# LSM6DS3Board1.net
KiCad netlist of a schematic drawn in EAGLE
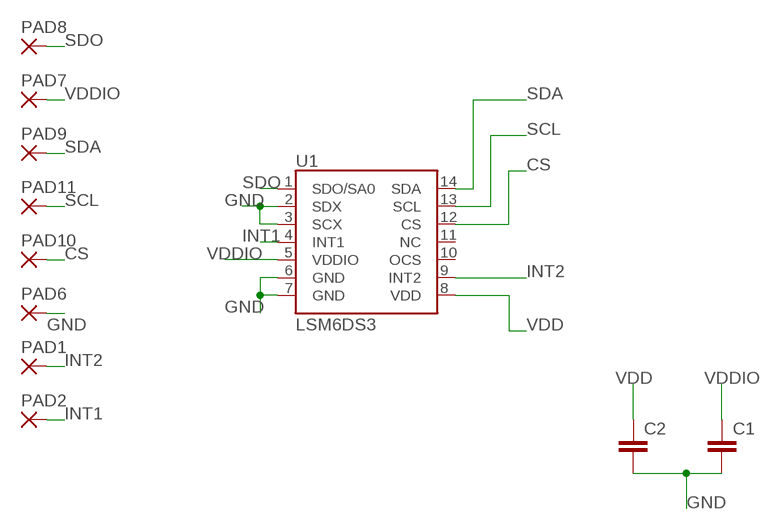
[diagram p0: schematic, sheet 1]

(export (version "E")
  (design (tool "Eeschema 10.0.6"))
  (components
    (comp (ref "C1")
      (value "C-EUC0603")
      (footprint "eagle-import:C0603")
      (libsource (lib "eagle-import") (part "C-EUC0603"))
    )
    (comp (ref "C2")
      (value "C-EUC0603")
      (footprint "eagle-import:C0603")
      (libsource (lib "eagle-import") (part "C-EUC0603"))
    )
    (comp (ref "PAD1")
      (value "1,6/0,8")
      (footprint "eagle-import:1,6_0,8")
      (libsource (lib "eagle-import") (part "1,6/0,8"))
    )
    (comp (ref "PAD2")
      (value "1,6/0,8")
      (footprint "eagle-import:1,6_0,8")
      (libsource (lib "eagle-import") (part "1,6/0,8"))
    )
    (comp (ref "PAD6")
      (value "1,6/0,8")
      (footprint "eagle-import:1,6_0,8")
      (libsource (lib "eagle-import") (part "1,6/0,8"))
    )
    (comp (ref "PAD7")
      (value "1,6/0,8")
      (footprint "eagle-import:1,6_0,8")
      (libsource (lib "eagle-import") (part "1,6/0,8"))
    )
    (comp (ref "PAD8")
      (value "1,6/0,8")
      (footprint "eagle-import:1,6_0,8")
      (libsource (lib "eagle-import") (part "1,6/0,8"))
    )
    (comp (ref "PAD9")
      (value "1,6/0,8")
      (footprint "eagle-import:1,6_0,8")
      (libsource (lib "eagle-import") (part "1,6/0,8"))
    )
    (comp (ref "PAD10")
      (value "1,6/0,8")
      (footprint "eagle-import:1,6_0,8")
      (libsource (lib "eagle-import") (part "1,6/0,8"))
    )
    (comp (ref "PAD11")
      (value "1,6/0,8")
      (footprint "eagle-import:1,6_0,8")
      (libsource (lib "eagle-import") (part "1,6/0,8"))
    )
    (comp (ref "U1")
      (value "LSM6DS3")
      (footprint "eagle-import:LGA14L")
      (libsource (lib "eagle-import") (part "LSM6DS3"))
    )
  )
  (nets
    (net (code "1") (name "/CS") (class "Default")
      (node (ref "PAD10") (pin "1") (pinfunction "P_1") (pintype "passive"))
      (node (ref "U1") (pin "12") (pinfunction "CS_12") (pintype "bidirectional"))
    )
    (net (code "2") (name "/GND") (class "Default")
      (node (ref "C1") (pin "2") (pinfunction "2_2") (pintype "passive"))
      (node (ref "C2") (pin "2") (pinfunction "2_2") (pintype "passive"))
      (node (ref "PAD6") (pin "1") (pinfunction "P_1") (pintype "passive"))
      (node (ref "U1") (pin "2") (pinfunction "SDX_2") (pintype "bidirectional"))
      (node (ref "U1") (pin "3") (pinfunction "SCX_3") (pintype "bidirectional"))
      (node (ref "U1") (pin "6") (pinfunction "GND_6") (pintype "bidirectional"))
      (node (ref "U1") (pin "7") (pinfunction "GND_7") (pintype "bidirectional"))
    )
    (net (code "3") (name "/INT1") (class "Default")
      (node (ref "PAD2") (pin "1") (pinfunction "P_1") (pintype "passive"))
      (node (ref "U1") (pin "4") (pinfunction "INT1_4") (pintype "bidirectional"))
    )
    (net (code "4") (name "/INT2") (class "Default")
      (node (ref "PAD1") (pin "1") (pinfunction "P_1") (pintype "passive"))
      (node (ref "U1") (pin "9") (pinfunction "INT2_9") (pintype "bidirectional"))
    )
    (net (code "5") (name "/SCL") (class "Default")
      (node (ref "PAD11") (pin "1") (pinfunction "P_1") (pintype "passive"))
      (node (ref "U1") (pin "13") (pinfunction "SCL_13") (pintype "bidirectional"))
    )
    (net (code "6") (name "/SDA") (class "Default")
      (node (ref "PAD9") (pin "1") (pinfunction "P_1") (pintype "passive"))
      (node (ref "U1") (pin "14") (pinfunction "SDA_14") (pintype "bidirectional"))
    )
    (net (code "7") (name "/SDO") (class "Default")
      (node (ref "PAD8") (pin "1") (pinfunction "P_1") (pintype "passive"))
      (node (ref "U1") (pin "1") (pinfunction "SDO/SA0_1") (pintype "bidirectional"))
    )
    (net (code "8") (name "/VDD") (class "Default")
      (node (ref "C2") (pin "1") (pinfunction "1_1") (pintype "passive"))
      (node (ref "U1") (pin "8") (pinfunction "VDD_8") (pintype "bidirectional"))
    )
    (net (code "9") (name "/VDDIO") (class "Default")
      (node (ref "C1") (pin "1") (pinfunction "1_1") (pintype "passive"))
      (node (ref "PAD7") (pin "1") (pinfunction "P_1") (pintype "passive"))
      (node (ref "U1") (pin "5") (pinfunction "VDDIO_5") (pintype "bidirectional"))
    )
    (net (code "10") (name "unconnected-(U1-NC-Pad11)") (class "Default")
      (node (ref "U1") (pin "11") (pinfunction "NC_11") (pintype "bidirectional"))
    )
    (net (code "11") (name "unconnected-(U1-OCS-Pad10)") (class "Default")
      (node (ref "U1") (pin "10") (pinfunction "OCS_10") (pintype "bidirectional"))
    )
  )
)
